# power_if.net
KiCad netlist of a schematic drawn in EAGLE
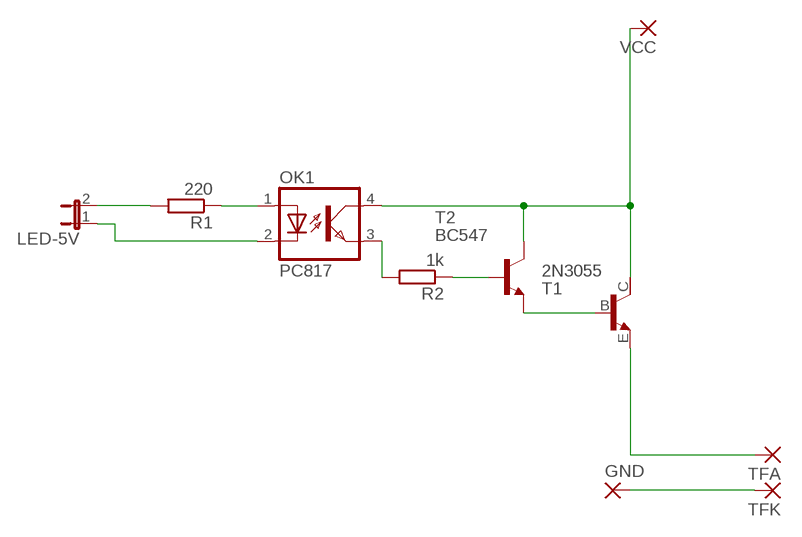
[diagram p0: schematic, sheet 1]

(export (version "E")
  (design (tool "Eeschema 10.0.6"))
  (components
    (comp (ref "GND")
      (value "3,81/1,4")
      (footprint "eagle-import:3,81_1,4")
      (libsource (lib "eagle-import") (part "3,81/1,4"))
    )
    (comp (ref "LED-5V")
      (value "JP1E")
      (footprint "eagle-import:JP1")
      (libsource (lib "eagle-import") (part "JP1E"))
    )
    (comp (ref "OK1")
      (value "PC817")
      (footprint "eagle-import:DIL04")
      (fields (field (name "MPN") "PC817X4J000F"))
      (libsource (lib "eagle-import") (part "PC817"))
    )
    (comp (ref "R1")
      (value "220")
      (footprint "eagle-import:0207_10")
      (libsource (lib "eagle-import") (part "R-EU_0207/10"))
    )
    (comp (ref "R2")
      (value "1k")
      (footprint "eagle-import:0207_10")
      (libsource (lib "eagle-import") (part "R-EU_0207/10"))
    )
    (comp (ref "T1")
      (value "2N3055")
      (footprint "eagle-import:TO3")
      (libsource (lib "eagle-import") (part "2N3055"))
    )
    (comp (ref "T2")
      (value "BC547")
      (footprint "eagle-import:TO92")
      (libsource (lib "eagle-import") (part "BC547"))
    )
    (comp (ref "TFA")
      (value "3,81/1,4")
      (footprint "eagle-import:3,81_1,4")
      (libsource (lib "eagle-import") (part "3,81/1,4"))
    )
    (comp (ref "TFK")
      (value "3,81/1,4")
      (footprint "eagle-import:3,81_1,4")
      (libsource (lib "eagle-import") (part "3,81/1,4"))
    )
    (comp (ref "VCC")
      (value "3,81/1,4")
      (footprint "eagle-import:3,81_1,4")
      (libsource (lib "eagle-import") (part "3,81/1,4"))
    )
  )
  (nets
    (net (code "1") (name "Net-(GND-P)") (class "Default")
      (node (ref "GND") (pin "1") (pinfunction "P_1") (pintype "passive"))
      (node (ref "TFK") (pin "1") (pinfunction "P_1") (pintype "passive"))
    )
    (net (code "2") (name "Net-(LED-5V-Pad2)") (class "Default")
      (node (ref "LED-5V") (pin "2") (pinfunction "2_2") (pintype "passive"))
      (node (ref "R1") (pin "2") (pinfunction "2_2") (pintype "passive"))
    )
    (net (code "3") (name "Net-(OK1-A)") (class "Default")
      (node (ref "OK1") (pin "1") (pinfunction "A_1") (pintype "passive"))
      (node (ref "R1") (pin "1") (pinfunction "1_1") (pintype "passive"))
    )
    (net (code "4") (name "Net-(OK1-C)") (class "Default")
      (node (ref "LED-5V") (pin "1") (pinfunction "1_1") (pintype "passive"))
      (node (ref "OK1") (pin "2") (pinfunction "C_2") (pintype "passive"))
    )
    (net (code "5") (name "Net-(OK1-COL)") (class "Default")
      (node (ref "OK1") (pin "4") (pinfunction "COL_4") (pintype "passive"))
      (node (ref "T1") (pin "C") (pinfunction "C_C") (pintype "passive"))
      (node (ref "T2") (pin "3") (pinfunction "C_3") (pintype "passive"))
      (node (ref "VCC") (pin "1") (pinfunction "P_1") (pintype "passive"))
    )
    (net (code "6") (name "Net-(OK1-EMIT)") (class "Default")
      (node (ref "OK1") (pin "3") (pinfunction "EMIT_3") (pintype "passive"))
      (node (ref "R2") (pin "2") (pinfunction "2_2") (pintype "passive"))
    )
    (net (code "7") (name "Net-(T2-B)") (class "Default")
      (node (ref "R2") (pin "1") (pinfunction "1_1") (pintype "passive"))
      (node (ref "T2") (pin "2") (pinfunction "B_2") (pintype "passive"))
    )
    (net (code "8") (name "Net-(T2-E)") (class "Default")
      (node (ref "T1") (pin "B") (pinfunction "B_B") (pintype "passive"))
      (node (ref "T2") (pin "1") (pinfunction "E_1") (pintype "passive"))
    )
    (net (code "9") (name "Net-(TFA-P)") (class "Default")
      (node (ref "T1") (pin "E") (pinfunction "E_E") (pintype "passive"))
      (node (ref "TFA") (pin "1") (pinfunction "P_1") (pintype "passive"))
    )
    (net (code "10") (name "unconnected-(T1-C-PadC{slash})") (class "Default")
      (node (ref "T1") (pin "C/") (pinfunction "C_C/") (pintype "passive"))
    )
  )
)
